# Monarch.net
KiCad netlist of a schematic drawn in Altium Designer
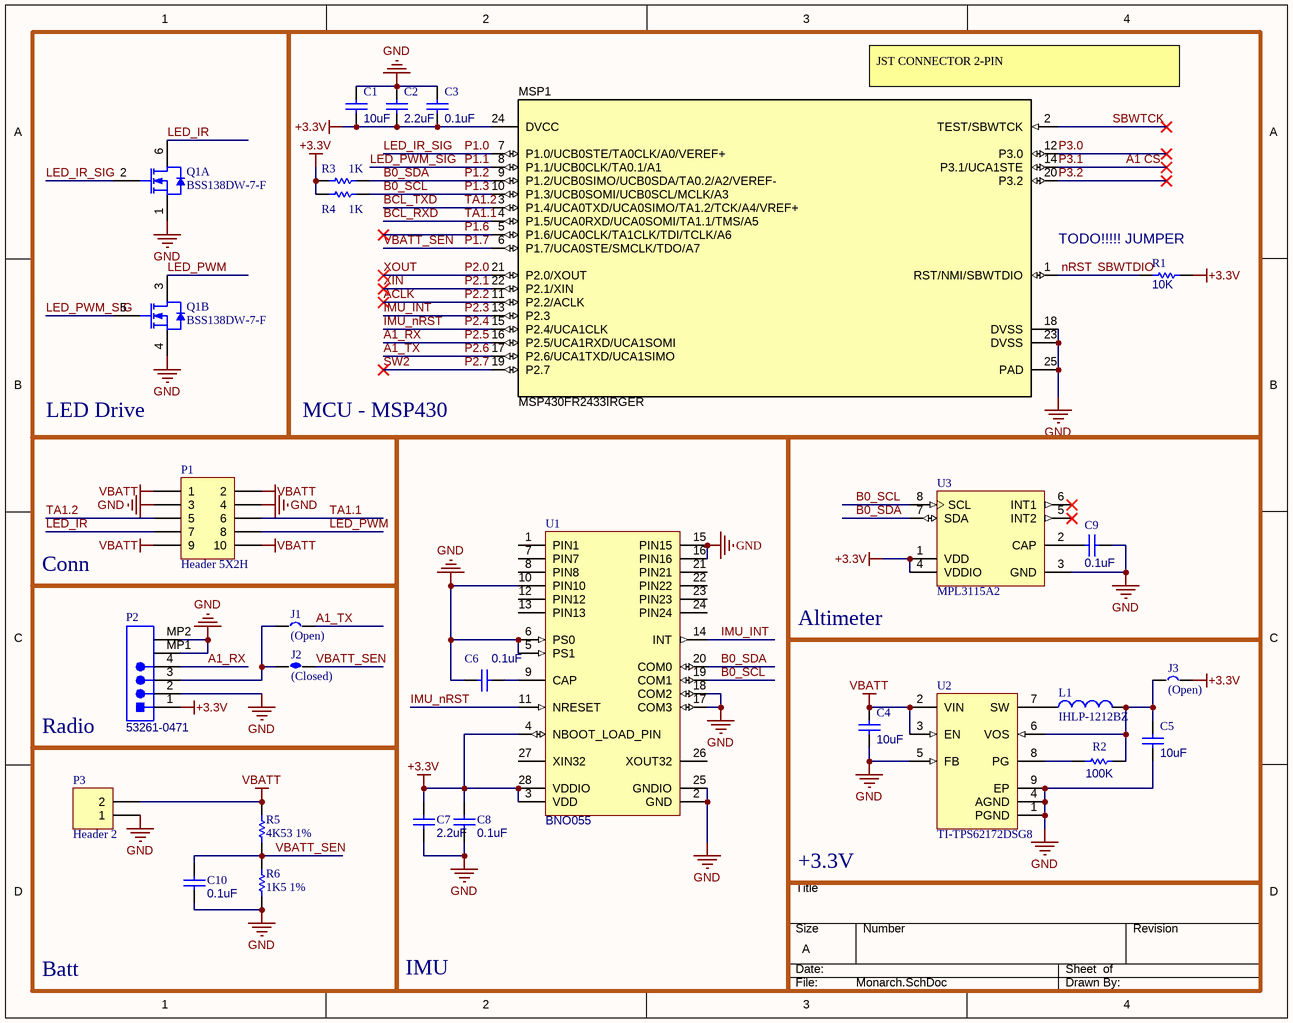
[diagram p0: Monarch.SchDoc]

(export (version "E")
  (design (tool "Eeschema 10.0.6"))
  (components
    (comp (ref "C1")
      (value "10uF")
      (footprint "CAPC0805(2012)100_L")
      (description "CAP 10uF 16V ±10% 0805 (2012 Metric) Thickness 1mm SMD")
      (fields (field (name "TOLERANCE") "Â±10%"))
      (libsource (lib "Altium Content Vault") (part "CAP"))
    )
    (comp (ref "C2")
      (value "2.2uF")
      (footprint "CAPC0603(1608)100_L")
      (description "CAP 2.2uF 16V ±10% 0603 (1608 Metric) Thickness 1mm SMD")
      (fields (field (name "TOLERANCE") "Â±10%"))
      (libsource (lib "Altium Content Vault") (part "CAP"))
    )
    (comp (ref "C3")
      (value "0.1uF")
      (footprint "CAPC0402(1005)60_L")
      (description "CAP 100nF 16V ±10% 0402 (1005 Metric) Thickness 0.6mm SMD")
      (fields (field (name "TOLERANCE") "Â±10%"))
      (libsource (lib "Altium Content Vault") (part "CAP"))
    )
    (comp (ref "C4")
      (value "10uF")
      (footprint "CAPC0805(2012)100_L")
      (description "CAP 10uF 16V ±10% 0805 (2012 Metric) Thickness 1mm SMD")
      (fields (field (name "TOLERANCE") "Â±10%"))
      (libsource (lib "Altium Content Vault") (part "CAP"))
    )
    (comp (ref "C5")
      (value "10uF")
      (footprint "CAPC0805(2012)100_L")
      (description "CAP 10uF 16V ±10% 0805 (2012 Metric) Thickness 1mm SMD")
      (fields (field (name "TOLERANCE") "Â±10%"))
      (libsource (lib "Altium Content Vault") (part "CAP"))
    )
    (comp (ref "C6")
      (value "0.1uF")
      (footprint "CAPC0402(1005)60_L")
      (description "CAP 100nF 16V ±10% 0402 (1005 Metric) Thickness 0.6mm SMD")
      (fields (field (name "TOLERANCE") "Â±10%"))
      (libsource (lib "Altium Content Vault") (part "CAP"))
    )
    (comp (ref "C7")
      (value "2.2uF")
      (footprint "CAPC0603(1608)100_L")
      (description "CAP 2.2uF 16V ±10% 0603 (1608 Metric) Thickness 1mm SMD")
      (fields (field (name "TOLERANCE") "Â±10%"))
      (libsource (lib "Altium Content Vault") (part "CAP"))
    )
    (comp (ref "C8")
      (value "0.1uF")
      (footprint "CAPC0402(1005)60_L")
      (description "CAP 100nF 16V ±10% 0402 (1005 Metric) Thickness 0.6mm SMD")
      (fields (field (name "TOLERANCE") "Â±10%"))
      (libsource (lib "Altium Content Vault") (part "CAP"))
    )
    (comp (ref "C9")
      (value "0.1uF")
      (footprint "CAPC0402(1005)60_L")
      (description "CAP 100nF 16V ±10% 0402 (1005 Metric) Thickness 0.6mm SMD")
      (fields (field (name "TOLERANCE") "Â±10%"))
      (libsource (lib "Altium Content Vault") (part "CAP"))
    )
    (comp (ref "C10")
      (value "0.1uF")
      (footprint "CAPC0402(1005)60_L")
      (description "CAP 100nF 16V ±10% 0402 (1005 Metric) Thickness 0.6mm SMD")
      (fields (field (name "TOLERANCE") "Â±10%"))
      (libsource (lib "Altium Content Vault") (part "CAP"))
    )
    (comp (ref "J1")
      (value "(Open)")
      (footprint "Solder Jumper")
      (description "Jumper")
      (libsource (lib "CMR_PCB_Components") (part "Jumper"))
    )
    (comp (ref "J2")
      (value "(Closed)")
      (footprint "Solder Jumper - Closed")
      (description "Jumper")
      (libsource (lib "CMR_PCB_Components") (part "Jumper Closed"))
    )
    (comp (ref "J3")
      (value "(Open)")
      (footprint "Solder Jumper")
      (description "Jumper")
      (libsource (lib "CMR_PCB_Components") (part "Jumper"))
    )
    (comp (ref "L1")
      (value "IHLP-1212BZ")
      (footprint "IHLP-1212BZ")
      (description "IHLP-1212BZ\r\n2.2uH")
      (fields (field (name "PUBLISHER") "Altium Limited"))
      (libsource (lib "Monarch") (part "IHLP-1212BZ"))
    )
    (comp (ref "MSP1")
      (value "MSP430FR2433IRGER")
      (footprint "RGE0024H")
      (fields
        (field (name "ALTERNATE PARTNUMBER") "MSP430FR2433IRGET")
        (field (name "MANUFACTURER") "Texas Instruments")
        (field (name "SYMBOLCREATOR") "Altium")
        (field (name "PUBLISHER") "Texas Instruments")
      )
      (libsource (lib "Monarch") (part "MSP430FR2433IRGER"))
    )
    (comp (ref "P1")
      (value "Header 5X2H")
      (footprint "HDR2X5H")
      (description "Header, 5-Pin, Dual row, Right Angle")
      (fields (field (name "PUBLISHER") "Altium Limited"))
      (libsource (lib "Monarch") (part "Header 5X2H"))
    )
    (comp (ref "P2")
      (value "53261-0471")
      (footprint "MOLEX-53261-0471_V")
      (description "Male Header, Pitch 1.25 mm, 1 x 4 Position, Height 3.4 mm, -40 to 85 degC, RoHS, Tape and Reel")
      (fields (field (name "MANUFACTURER") "Molex"))
      (libsource (lib "Altium Content Vault") (part "CN-1P-2M-R4_A"))
    )
    (comp (ref "P3")
      (value "Header 2")
      (footprint "HDR1X2")
      (description "Header, 2-Pin")
      (fields (field (name "PUBLISHER") "Altium Limited"))
      (libsource (lib "Miscellaneous Connectors") (part "Header 2"))
    )
    (comp (ref "Q1")
      (value "BSS138DW-7-F")
      (footprint "DIOD-SOT363-6_V")
      (fields (field (name "MANUFACTURER") "DiodesIncorporated"))
      (libsource (lib "Altium Content Vault") (part "NEMOS-SGD-DSG-6"))
    )
    (comp (ref "R1")
      (value "10K")
      (footprint "RESC0402(1005)_L")
      (description "10K 0.063W 1% 0402 (1005 Metric)  SMD")
      (fields (field (name "TOLERANCE") "1 %") (field (name "POWER") "0.063 W"))
      (libsource (lib "Altium Content Vault") (part "RES"))
    )
    (comp (ref "R2")
      (value "100K")
      (footprint "RESC0402(1005)_L")
      (description "100K 0.063W 1% 0402 (1005 Metric)  SMD")
      (fields (field (name "POWER") "0.063 W") (field (name "TOLERANCE") "1 %"))
      (libsource (lib "Altium Content Vault") (part "RES"))
    )
    (comp (ref "R3")
      (value "1K")
      (footprint "RESC0402(1005)_L")
      (description "1K 0.063W 1% 0402 (1005 Metric)  SMD")
      (fields (field (name "TOLERANCE") "1 %") (field (name "POWER") "0.063 W"))
      (libsource (lib "Altium Content Vault") (part "RES"))
    )
    (comp (ref "R4")
      (value "1K")
      (footprint "RESC0402(1005)_L")
      (description "1K 0.063W 1% 0402 (1005 Metric)  SMD")
      (fields (field (name "TOLERANCE") "1 %") (field (name "POWER") "0.063 W"))
      (libsource (lib "Altium Content Vault") (part "RES"))
    )
    (comp (ref "R5")
      (value "4K53 1%")
      (footprint "RESC0402(1005)_L")
      (description "4K53 0.063W 1% 0402 (1005 Metric)  SMD")
      (fields (field (name "POWER") "0.063 W") (field (name "TOLERANCE") "1 %"))
      (libsource (lib "Altium Content Vault") (part "RES"))
    )
    (comp (ref "R6")
      (value "1K5 1%")
      (footprint "RESC0402(1005)_L")
      (description "1K5 0.063W 1% 0402 (1005 Metric)  SMD")
      (fields (field (name "TOLERANCE") "1 %") (field (name "POWER") "0.063 W"))
      (libsource (lib "Altium Content Vault") (part "RES"))
    )
    (comp (ref "U1")
      (value "BNO055")
      (footprint "BOSC-LGA-28_N")
      (fields (field (name "MANUFACTURER") "Bosch Sensortec"))
      (libsource (lib "Altium Content Vault") (part "BOSC-BNO055-LGA-28"))
    )
    (comp (ref "U2")
      (value "TI-TPS62172DSG8")
      (footprint "DSG0008A_V")
      (libsource (lib "Monarch") (part "TI-TPS62172DSG8-1600X900TP"))
    )
    (comp (ref "U3")
      (value "MPL3115A2")
      (footprint "FRES-2153-01_V")
      (description "Xtrinsic I2C Precision Altimeter, 1.95 to 3.6 V, -40 to 85 degC, 8-Pin LGA (2153-01), RoHS, Tray")
      (fields (field (name "MANUFACTURER") "Freescale Semiconductor"))
      (libsource (lib "Altium Content Vault") (part "FRES-MPL3115A2-8"))
    )
  )
  (nets
    (net (code "1") (name "+3.3V") (class "Default")
      (node (ref "C1") (pin "1") (pinfunction "1_1") (pintype "passive"))
      (node (ref "C2") (pin "1") (pinfunction "1_1") (pintype "passive"))
      (node (ref "C3") (pin "1") (pinfunction "1_1") (pintype "passive"))
      (node (ref "C7") (pin "2") (pinfunction "2_2") (pintype "passive"))
      (node (ref "C8") (pin "2") (pinfunction "2_2") (pintype "passive"))
      (node (ref "J3") (pin "2") (pinfunction "2_2") (pintype "passive"))
      (node (ref "MSP1") (pin "24") (pinfunction "DVCC_24") (pintype "power_in"))
      (node (ref "P2") (pin "1") (pinfunction "1_1") (pintype "passive"))
      (node (ref "R1") (pin "2") (pinfunction "2_2") (pintype "passive"))
      (node (ref "R3") (pin "1") (pinfunction "1_1") (pintype "passive"))
      (node (ref "R4") (pin "1") (pinfunction "1_1") (pintype "passive"))
      (node (ref "U1") (pin "28") (pinfunction "VDDIO_28") (pintype "power_in"))
      (node (ref "U1") (pin "3") (pinfunction "VDD_3") (pintype "power_in"))
      (node (ref "U1") (pin "4") (pinfunction "NBOOT_LOAD_PIN_4") (pintype "bidirectional"))
      (node (ref "U3") (pin "1") (pinfunction "VDD_1") (pintype "power_in"))
      (node (ref "U3") (pin "4") (pinfunction "VDDIO_4") (pintype "power_in"))
    )
    (net (code "2") (name "/A1 CS") (class "Default")
      (node (ref "MSP1") (pin "14") (pinfunction "P3.1/UCA1STE_14") (pintype "bidirectional+no_connect"))
    )
    (net (code "3") (name "/A1_RX") (class "Default")
      (node (ref "MSP1") (pin "16") (pinfunction "P2.5/UCA1RXD/UCA1SOMI_16") (pintype "bidirectional"))
      (node (ref "P2") (pin "4") (pinfunction "4_4") (pintype "passive"))
    )
    (net (code "4") (name "/A1_TX") (class "Default")
      (node (ref "J1") (pin "2") (pinfunction "2_2") (pintype "passive"))
      (node (ref "MSP1") (pin "17") (pinfunction "P2.6/UCA1TXD/UCA1SIMO_17") (pintype "bidirectional"))
    )
    (net (code "5") (name "/ACLK") (class "Default")
      (node (ref "MSP1") (pin "11") (pinfunction "P2.2/ACLK_11") (pintype "bidirectional+no_connect"))
    )
    (net (code "6") (name "/B0_SCL") (class "Default")
      (node (ref "MSP1") (pin "10") (pinfunction "P1.3/UCB0SOMI/UCB0SCL/MCLK/A3_10") (pintype "bidirectional"))
      (node (ref "R4") (pin "2") (pinfunction "2_2") (pintype "passive"))
      (node (ref "U1") (pin "19") (pinfunction "COM1_19") (pintype "bidirectional"))
      (node (ref "U3") (pin "8") (pinfunction "SCL_8") (pintype "input"))
    )
    (net (code "7") (name "/B0_SDA") (class "Default")
      (node (ref "MSP1") (pin "9") (pinfunction "P1.2/UCB0SIMO/UCB0SDA/TA0.2/A2/VEREF-_9") (pintype "bidirectional"))
      (node (ref "R3") (pin "2") (pinfunction "2_2") (pintype "passive"))
      (node (ref "U1") (pin "20") (pinfunction "COM0_20") (pintype "bidirectional"))
      (node (ref "U3") (pin "7") (pinfunction "SDA_7") (pintype "bidirectional"))
    )
    (net (code "8") (name "/BCL_RXD") (class "Default")
      (node (ref "MSP1") (pin "4") (pinfunction "P1.5/UCA0RXD/UCA0SOMI/TA1.1/TMS/A5_4") (pintype "bidirectional"))
      (node (ref "P1") (pin "6") (pinfunction "6_6") (pintype "passive"))
    )
    (net (code "9") (name "/BCL_TXD") (class "Default")
      (node (ref "MSP1") (pin "3") (pinfunction "P1.4/UCA0TXD/UCA0SIMO/TA1.2/TCK/A4/VREF+_3") (pintype "bidirectional"))
      (node (ref "P1") (pin "5") (pinfunction "5_5") (pintype "passive"))
    )
    (net (code "10") (name "/IMU_INT") (class "Default")
      (node (ref "MSP1") (pin "13") (pinfunction "P2.3_13") (pintype "bidirectional"))
      (node (ref "U1") (pin "14") (pinfunction "INT_14") (pintype "output"))
    )
    (net (code "11") (name "/IMU_nRST") (class "Default")
      (node (ref "MSP1") (pin "15") (pinfunction "P2.4/UCA1CLK_15") (pintype "bidirectional"))
      (node (ref "U1") (pin "11") (pinfunction "NRESET_11") (pintype "input"))
    )
    (net (code "12") (name "/LED_IR") (class "Default")
      (node (ref "P1") (pin "7") (pinfunction "7_7") (pintype "passive"))
      (node (ref "Q1") (pin "6") (pinfunction "D1_6") (pintype "passive"))
    )
    (net (code "13") (name "/LED_IR_SIG") (class "Default")
      (node (ref "MSP1") (pin "7") (pinfunction "P1.0/UCB0STE/TA0CLK/A0/VEREF+_7") (pintype "bidirectional"))
      (node (ref "Q1") (pin "2") (pinfunction "G1_2") (pintype "passive"))
    )
    (net (code "14") (name "/LED_PWM") (class "Default")
      (node (ref "P1") (pin "8") (pinfunction "8_8") (pintype "passive"))
      (node (ref "Q1") (pin "3") (pinfunction "D2_3") (pintype "passive"))
    )
    (net (code "15") (name "/LED_PWM_SIG") (class "Default")
      (node (ref "MSP1") (pin "8") (pinfunction "P1.1/UCB0CLK/TA0.1/A1_8") (pintype "bidirectional"))
      (node (ref "Q1") (pin "5") (pinfunction "G2_5") (pintype "passive"))
    )
    (net (code "16") (name "/P1.6") (class "Default")
      (node (ref "MSP1") (pin "5") (pinfunction "P1.6/UCA0CLK/TA1CLK/TDI/TCLK/A6_5") (pintype "bidirectional+no_connect"))
    )
    (net (code "17") (name "/P1.7") (class "Default")
      (node (ref "C10") (pin "1") (pinfunction "1_1") (pintype "passive"))
      (node (ref "J2") (pin "2") (pinfunction "2_2") (pintype "passive"))
      (node (ref "MSP1") (pin "6") (pinfunction "P1.7/UCA0STE/SMCLK/TDO/A7_6") (pintype "bidirectional"))
      (node (ref "R5") (pin "1") (pinfunction "1_1") (pintype "passive"))
      (node (ref "R6") (pin "2") (pinfunction "2_2") (pintype "passive"))
    )
    (net (code "18") (name "/P2.0") (class "Default")
      (node (ref "MSP1") (pin "21") (pinfunction "P2.0/XOUT_21") (pintype "bidirectional+no_connect"))
    )
    (net (code "19") (name "/P2.1") (class "Default")
      (node (ref "MSP1") (pin "22") (pinfunction "P2.1/XIN_22") (pintype "bidirectional+no_connect"))
    )
    (net (code "20") (name "/P2.7") (class "Default")
      (node (ref "MSP1") (pin "19") (pinfunction "P2.7_19") (pintype "bidirectional+no_connect"))
    )
    (net (code "21") (name "/P3.0") (class "Default")
      (node (ref "MSP1") (pin "12") (pinfunction "P3.0_12") (pintype "bidirectional+no_connect"))
    )
    (net (code "22") (name "/P3.2") (class "Default")
      (node (ref "MSP1") (pin "20") (pinfunction "P3.2_20") (pintype "bidirectional+no_connect"))
    )
    (net (code "23") (name "/SBWTCK") (class "Default")
      (node (ref "MSP1") (pin "2") (pinfunction "TEST/SBWTCK_2") (pintype "input+no_connect"))
    )
    (net (code "24") (name "/SBWTDIO") (class "Default")
      (node (ref "MSP1") (pin "1") (pinfunction "RST/NMI/SBWTDIO_1") (pintype "bidirectional"))
      (node (ref "R1") (pin "1") (pinfunction "1_1") (pintype "passive"))
    )
    (net (code "25") (name "GND") (class "Default")
      (node (ref "C1") (pin "2") (pinfunction "2_2") (pintype "passive"))
      (node (ref "C10") (pin "2") (pinfunction "2_2") (pintype "passive"))
      (node (ref "C2") (pin "2") (pinfunction "2_2") (pintype "passive"))
      (node (ref "C3") (pin "2") (pinfunction "2_2") (pintype "passive"))
      (node (ref "C4") (pin "1") (pinfunction "1_1") (pintype "passive"))
      (node (ref "C5") (pin "1") (pinfunction "1_1") (pintype "passive"))
      (node (ref "C6") (pin "2") (pinfunction "2_2") (pintype "passive"))
      (node (ref "C7") (pin "1") (pinfunction "1_1") (pintype "passive"))
      (node (ref "C8") (pin "1") (pinfunction "1_1") (pintype "passive"))
      (node (ref "C9") (pin "1") (pinfunction "1_1") (pintype "passive"))
      (node (ref "MSP1") (pin "18") (pinfunction "DVSS_18") (pintype "power_in"))
      (node (ref "MSP1") (pin "23") (pinfunction "DVSS_23") (pintype "power_in"))
      (node (ref "MSP1") (pin "25") (pinfunction "PAD_25") (pintype "power_in"))
      (node (ref "P1") (pin "3") (pinfunction "3_3") (pintype "passive"))
      (node (ref "P1") (pin "4") (pinfunction "4_4") (pintype "passive"))
      (node (ref "P2") (pin "2") (pinfunction "2_2") (pintype "passive"))
      (node (ref "P2") (pin "MP1") (pinfunction "MP1_MP1") (pintype "passive"))
      (node (ref "P2") (pin "MP2") (pinfunction "MP2_MP2") (pintype "passive"))
      (node (ref "P3") (pin "1") (pinfunction "1_1") (pintype "passive"))
      (node (ref "Q1") (pin "1") (pinfunction "S1_1") (pintype "passive"))
      (node (ref "Q1") (pin "4") (pinfunction "S2_4") (pintype "passive"))
      (node (ref "R6") (pin "1") (pinfunction "1_1") (pintype "passive"))
      (node (ref "U1") (pin "10") (pinfunction "PIN10_10") (pintype "power_in"))
      (node (ref "U1") (pin "15") (pinfunction "PIN15_15") (pintype "power_in"))
      (node (ref "U1") (pin "16") (pinfunction "PIN16_16") (pintype "power_in"))
      (node (ref "U1") (pin "17") (pinfunction "COM3_17") (pintype "bidirectional"))
      (node (ref "U1") (pin "18") (pinfunction "COM2_18") (pintype "bidirectional"))
      (node (ref "U1") (pin "2") (pinfunction "GND_2") (pintype "power_in"))
      (node (ref "U1") (pin "25") (pinfunction "GNDIO_25") (pintype "power_in"))
      (node (ref "U1") (pin "5") (pinfunction "PS1_5") (pintype "input"))
      (node (ref "U1") (pin "6") (pinfunction "PS0_6") (pintype "input"))
      (node (ref "U2") (pin "1") (pinfunction "PGND_1") (pintype "power_in"))
      (node (ref "U2") (pin "4") (pinfunction "AGND_4") (pintype "power_in"))
      (node (ref "U2") (pin "5") (pinfunction "FB_5") (pintype "input"))
      (node (ref "U2") (pin "9") (pinfunction "EP_9") (pintype "power_in"))
      (node (ref "U3") (pin "3") (pinfunction "GND_3") (pintype "power_in"))
    )
    (net (code "26") (name "Net-(J1-Pad1)") (class "Default")
      (node (ref "J1") (pin "1") (pinfunction "1_1") (pintype "passive"))
      (node (ref "J2") (pin "1") (pinfunction "1_1") (pintype "passive"))
      (node (ref "P2") (pin "3") (pinfunction "3_3") (pintype "passive"))
    )
    (net (code "27") (name "Net-(U1-CAP)") (class "Default")
      (node (ref "C6") (pin "1") (pinfunction "1_1") (pintype "passive"))
      (node (ref "U1") (pin "9") (pinfunction "CAP_9") (pintype "passive"))
    )
    (net (code "28") (name "Net-(U2-PG)") (class "Default")
      (node (ref "R2") (pin "1") (pinfunction "1_1") (pintype "passive"))
      (node (ref "U2") (pin "8") (pinfunction "PG_8") (pintype "tri_state"))
    )
    (net (code "29") (name "Net-(U2-SW)") (class "Default")
      (node (ref "L1") (pin "1") (pinfunction "1_1") (pintype "passive"))
      (node (ref "U2") (pin "7") (pinfunction "SW_7") (pintype "power_in"))
    )
    (net (code "30") (name "Net-(U2-VOS)") (class "Default")
      (node (ref "C5") (pin "2") (pinfunction "2_2") (pintype "passive"))
      (node (ref "J3") (pin "1") (pinfunction "1_1") (pintype "passive"))
      (node (ref "L1") (pin "2") (pinfunction "2_2") (pintype "passive"))
      (node (ref "R2") (pin "2") (pinfunction "2_2") (pintype "passive"))
      (node (ref "U2") (pin "6") (pinfunction "VOS_6") (pintype "input"))
    )
    (net (code "31") (name "Net-(U3-CAP)") (class "Default")
      (node (ref "C9") (pin "2") (pinfunction "2_2") (pintype "passive"))
      (node (ref "U3") (pin "2") (pinfunction "CAP_2") (pintype "passive"))
    )
    (net (code "32") (name "VBATT") (class "Default")
      (node (ref "C4") (pin "2") (pinfunction "2_2") (pintype "passive"))
      (node (ref "P1") (pin "1") (pinfunction "1_1") (pintype "passive"))
      (node (ref "P1") (pin "10") (pinfunction "10_10") (pintype "passive"))
      (node (ref "P1") (pin "2") (pinfunction "2_2") (pintype "passive"))
      (node (ref "P1") (pin "9") (pinfunction "9_9") (pintype "passive"))
      (node (ref "P3") (pin "2") (pinfunction "2_2") (pintype "passive"))
      (node (ref "R5") (pin "2") (pinfunction "2_2") (pintype "passive"))
      (node (ref "U2") (pin "2") (pinfunction "VIN_2") (pintype "power_in"))
      (node (ref "U2") (pin "3") (pinfunction "EN_3") (pintype "input"))
    )
    (net (code "33") (name "unconnected-(U1-PIN1-Pad1)") (class "Default")
      (node (ref "U1") (pin "1") (pinfunction "PIN1_1") (pintype "passive"))
    )
    (net (code "34") (name "unconnected-(U1-PIN7-Pad7)") (class "Default")
      (node (ref "U1") (pin "7") (pinfunction "PIN7_7") (pintype "passive"))
    )
    (net (code "35") (name "unconnected-(U1-PIN8-Pad8)") (class "Default")
      (node (ref "U1") (pin "8") (pinfunction "PIN8_8") (pintype "passive"))
    )
    (net (code "36") (name "unconnected-(U1-PIN12-Pad12)") (class "Default")
      (node (ref "U1") (pin "12") (pinfunction "PIN12_12") (pintype "passive"))
    )
    (net (code "37") (name "unconnected-(U1-PIN13-Pad13)") (class "Default")
      (node (ref "U1") (pin "13") (pinfunction "PIN13_13") (pintype "passive"))
    )
    (net (code "38") (name "unconnected-(U1-PIN21-Pad21)") (class "Default")
      (node (ref "U1") (pin "21") (pinfunction "PIN21_21") (pintype "passive"))
    )
    (net (code "39") (name "unconnected-(U1-PIN22-Pad22)") (class "Default")
      (node (ref "U1") (pin "22") (pinfunction "PIN22_22") (pintype "passive"))
    )
    (net (code "40") (name "unconnected-(U1-PIN23-Pad23)") (class "Default")
      (node (ref "U1") (pin "23") (pinfunction "PIN23_23") (pintype "passive"))
    )
    (net (code "41") (name "unconnected-(U1-PIN24-Pad24)") (class "Default")
      (node (ref "U1") (pin "24") (pinfunction "PIN24_24") (pintype "passive"))
    )
    (net (code "42") (name "unconnected-(U1-XIN32-Pad27)") (class "Default")
      (node (ref "U1") (pin "27") (pinfunction "XIN32_27") (pintype "passive"))
    )
    (net (code "43") (name "unconnected-(U1-XOUT32-Pad26)") (class "Default")
      (node (ref "U1") (pin "26") (pinfunction "XOUT32_26") (pintype "passive"))
    )
    (net (code "44") (name "unconnected-(U3-INT1-Pad6)") (class "Default")
      (node (ref "U3") (pin "6") (pinfunction "INT1_6") (pintype "output+no_connect"))
    )
    (net (code "45") (name "unconnected-(U3-INT2-Pad5)") (class "Default")
      (node (ref "U3") (pin "5") (pinfunction "INT2_5") (pintype "output+no_connect"))
    )
  )
)
